# max14866.net
KiCad netlist of a schematic drawn in Altium Designer
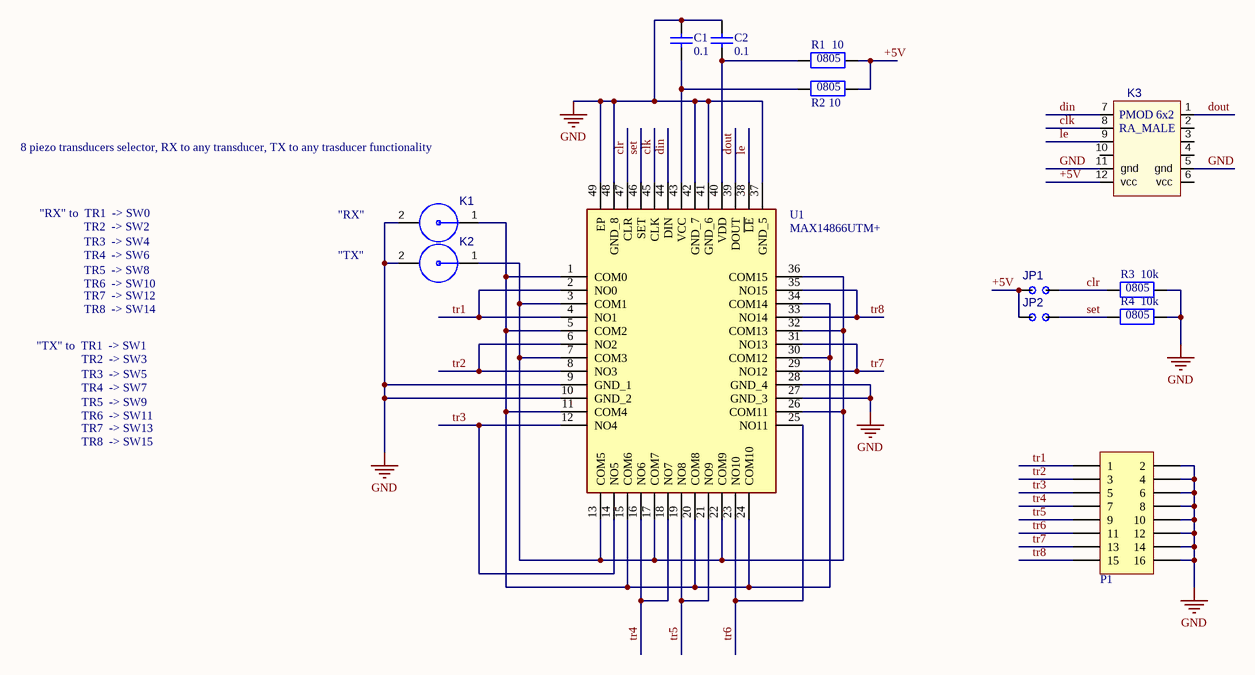
[diagram p0: max14866.SchDoc]

(export (version "E")
  (design (tool "Eeschema 10.0.6"))
  (components
    (comp (ref "C1")
      (value "0.1")
      (footprint "SM0805")
      (description "Capacitor")
      (fields (field (name "Comment") "cap0805") (field (name "PUBLISHER") "Altium Limited"))
      (libsource (lib "alt2017") (part "cap0805"))
    )
    (comp (ref "C2")
      (value "0.1")
      (footprint "SM0805")
      (description "Capacitor")
      (fields (field (name "Comment") "cap0805") (field (name "PUBLISHER") "Altium Limited"))
      (libsource (lib "alt2017") (part "cap0805"))
    )
    (comp (ref "JP1") (value "JUMPER2") (footprint "JUMPER2") (libsource (lib "alt2017") (part "JUMPER2")))
    (comp (ref "JP2") (value "JUMPER2") (footprint "JUMPER2") (libsource (lib "alt2017") (part "JUMPER2")))
    (comp (ref "K1")
      (value "SMA_MALE_with_NUT")
      (footprint "AMPHENOL_MALE")
      (libsource (lib "alt2017") (part "SMA_MALE_with_NUT"))
    )
    (comp (ref "K2")
      (value "SMA_MALE_with_NUT")
      (footprint "AMPHENOL_MALE")
      (libsource (lib "alt2017") (part "SMA_MALE_with_NUT"))
    )
    (comp (ref "K3")
      (value "PMOD_6x2_ra_male_mirrored")
      (footprint "PMOD_6x2_RA_MALE_MIRRORED")
      (description "PMOD_6x2_right_angle")
      (libsource (lib "alt2017") (part "PMOD_6x2_ra_male_mirrored"))
    )
    (comp (ref "P1")
      (value "2x8, 2.54mm vertical")
      (footprint "2x8 pin 2.54mm")
      (description "Header, 16-Pin")
      (fields (field (name "PUBLISHER") "Altium Limited"))
      (libsource (lib "alt2017") (part "2x8, 2.54mm, vertical"))
    )
    (comp (ref "R1")
      (value "10")
      (footprint "SM0805")
      (description "Resistor")
      (fields (field (name "Comment") "res0805_EU") (field (name "PUBLISHER") "Altium Limited"))
      (libsource (lib "alt2017") (part "res0805_EU"))
    )
    (comp (ref "R2")
      (value "10")
      (footprint "SM0805")
      (description "Resistor")
      (fields (field (name "Comment") "res0805_EU") (field (name "PUBLISHER") "Altium Limited"))
      (libsource (lib "alt2017") (part "res0805_EU"))
    )
    (comp (ref "R3")
      (value "10k")
      (footprint "SM0805")
      (description "Resistor")
      (fields (field (name "Comment") "res0805_EU") (field (name "PUBLISHER") "Altium Limited"))
      (libsource (lib "alt2017") (part "res0805_EU"))
    )
    (comp (ref "R4")
      (value "10k")
      (footprint "SM0805")
      (description "Resistor")
      (fields (field (name "Comment") "res0805_EU") (field (name "PUBLISHER") "Altium Limited"))
      (libsource (lib "alt2017") (part "res0805_EU"))
    )
    (comp (ref "U1")
      (value "MAX14866UTM+")
      (footprint "QFN50P700X700X80-49N")
      (description "Integrated Circuit")
      (fields (field (name "MOUSER PART NUMBER") "700-MAX14866UTM+"))
      (libsource (lib "alt2017") (part "MAX14866UTM+"))
    )
  )
  (nets
    (net (code "1") (name "/+5V") (class "Default")
      (node (ref "JP1") (pin "2") (pinfunction "2_2") (pintype "passive"))
      (node (ref "JP2") (pin "2") (pinfunction "2_2") (pintype "passive"))
      (node (ref "K3") (pin "12") (pinfunction "vcc_12") (pintype "passive"))
      (node (ref "R1") (pin "2") (pinfunction "2_2") (pintype "passive"))
      (node (ref "R2") (pin "2") (pinfunction "2_2") (pintype "passive"))
    )
    (net (code "2") (name "/clk") (class "Default")
      (node (ref "K3") (pin "8") (pinfunction "8_8") (pintype "passive"))
      (node (ref "U1") (pin "45") (pinfunction "CLK_45") (pintype "passive"))
    )
    (net (code "3") (name "/clr") (class "Default")
      (node (ref "JP1") (pin "1") (pinfunction "1_1") (pintype "passive"))
      (node (ref "R3") (pin "1") (pinfunction "1_1") (pintype "passive"))
      (node (ref "U1") (pin "47") (pinfunction "CLR_47") (pintype "passive"))
    )
    (net (code "4") (name "/din") (class "Default")
      (node (ref "K3") (pin "7") (pinfunction "7_7") (pintype "passive"))
      (node (ref "U1") (pin "44") (pinfunction "DIN_44") (pintype "passive"))
    )
    (net (code "5") (name "/dout") (class "Default")
      (node (ref "K3") (pin "1") (pinfunction "1_1") (pintype "passive"))
      (node (ref "U1") (pin "39") (pinfunction "DOUT_39") (pintype "passive"))
    )
    (net (code "6") (name "/le") (class "Default")
      (node (ref "K3") (pin "9") (pinfunction "9_9") (pintype "passive"))
      (node (ref "U1") (pin "38") (pinfunction "~{LE}_38") (pintype "passive"))
    )
    (net (code "7") (name "/set") (class "Default")
      (node (ref "JP2") (pin "1") (pinfunction "1_1") (pintype "passive"))
      (node (ref "R4") (pin "1") (pinfunction "1_1") (pintype "passive"))
      (node (ref "U1") (pin "46") (pinfunction "SET_46") (pintype "passive"))
    )
    (net (code "8") (name "/tr1") (class "Default")
      (node (ref "P1") (pin "1") (pinfunction "1_1") (pintype "passive"))
      (node (ref "U1") (pin "2") (pinfunction "NO0_2") (pintype "passive"))
      (node (ref "U1") (pin "4") (pinfunction "NO1_4") (pintype "passive"))
    )
    (net (code "9") (name "/tr2") (class "Default")
      (node (ref "P1") (pin "3") (pinfunction "3_3") (pintype "passive"))
      (node (ref "U1") (pin "6") (pinfunction "NO2_6") (pintype "passive"))
      (node (ref "U1") (pin "8") (pinfunction "NO3_8") (pintype "passive"))
    )
    (net (code "10") (name "/tr3") (class "Default")
      (node (ref "P1") (pin "5") (pinfunction "5_5") (pintype "passive"))
      (node (ref "U1") (pin "12") (pinfunction "NO4_12") (pintype "passive"))
      (node (ref "U1") (pin "14") (pinfunction "NO5_14") (pintype "passive"))
    )
    (net (code "11") (name "/tr4") (class "Default")
      (node (ref "P1") (pin "7") (pinfunction "7_7") (pintype "passive"))
      (node (ref "U1") (pin "16") (pinfunction "NO6_16") (pintype "passive"))
      (node (ref "U1") (pin "18") (pinfunction "NO7_18") (pintype "passive"))
    )
    (net (code "12") (name "/tr5") (class "Default")
      (node (ref "P1") (pin "9") (pinfunction "9_9") (pintype "passive"))
      (node (ref "U1") (pin "19") (pinfunction "NO8_19") (pintype "passive"))
      (node (ref "U1") (pin "21") (pinfunction "NO9_21") (pintype "passive"))
    )
    (net (code "13") (name "/tr6") (class "Default")
      (node (ref "P1") (pin "11") (pinfunction "11_11") (pintype "passive"))
      (node (ref "U1") (pin "23") (pinfunction "NO10_23") (pintype "passive"))
      (node (ref "U1") (pin "25") (pinfunction "NO11_25") (pintype "passive"))
    )
    (net (code "14") (name "/tr7") (class "Default")
      (node (ref "P1") (pin "13") (pinfunction "13_13") (pintype "passive"))
      (node (ref "U1") (pin "29") (pinfunction "NO12_29") (pintype "passive"))
      (node (ref "U1") (pin "31") (pinfunction "NO13_31") (pintype "passive"))
    )
    (net (code "15") (name "/tr8") (class "Default")
      (node (ref "P1") (pin "15") (pinfunction "15_15") (pintype "passive"))
      (node (ref "U1") (pin "33") (pinfunction "NO14_33") (pintype "passive"))
      (node (ref "U1") (pin "35") (pinfunction "NO15_35") (pintype "passive"))
    )
    (net (code "16") (name "GND") (class "Default")
      (node (ref "C1") (pin "2") (pinfunction "2_2") (pintype "passive"))
      (node (ref "C2") (pin "2") (pinfunction "2_2") (pintype "passive"))
      (node (ref "K1") (pin "2") (pinfunction "2_2") (pintype "passive"))
      (node (ref "K2") (pin "2") (pinfunction "2_2") (pintype "passive"))
      (node (ref "K3") (pin "11") (pinfunction "gnd_11") (pintype "passive"))
      (node (ref "K3") (pin "5") (pinfunction "gnd_5") (pintype "passive"))
      (node (ref "P1") (pin "10") (pinfunction "10_10") (pintype "passive"))
      (node (ref "P1") (pin "12") (pinfunction "12_12") (pintype "passive"))
      (node (ref "P1") (pin "14") (pinfunction "14_14") (pintype "passive"))
      (node (ref "P1") (pin "16") (pinfunction "16_16") (pintype "passive"))
      (node (ref "P1") (pin "2") (pinfunction "2_2") (pintype "passive"))
      (node (ref "P1") (pin "4") (pinfunction "4_4") (pintype "passive"))
      (node (ref "P1") (pin "6") (pinfunction "6_6") (pintype "passive"))
      (node (ref "P1") (pin "8") (pinfunction "8_8") (pintype "passive"))
      (node (ref "R3") (pin "2") (pinfunction "2_2") (pintype "passive"))
      (node (ref "R4") (pin "2") (pinfunction "2_2") (pintype "passive"))
      (node (ref "U1") (pin "10") (pinfunction "GND_2_10") (pintype "passive"))
      (node (ref "U1") (pin "27") (pinfunction "GND_3_27") (pintype "passive"))
      (node (ref "U1") (pin "28") (pinfunction "GND_4_28") (pintype "passive"))
      (node (ref "U1") (pin "37") (pinfunction "GND_5_37") (pintype "passive"))
      (node (ref "U1") (pin "41") (pinfunction "GND_6_41") (pintype "passive"))
      (node (ref "U1") (pin "42") (pinfunction "GND_7_42") (pintype "passive"))
      (node (ref "U1") (pin "48") (pinfunction "GND_8_48") (pintype "passive"))
      (node (ref "U1") (pin "49") (pinfunction "EP_49") (pintype "passive"))
      (node (ref "U1") (pin "9") (pinfunction "GND_1_9") (pintype "passive"))
    )
    (net (code "17") (name "Net-(U1-COM0)") (class "Default")
      (node (ref "K1") (pin "1") (pinfunction "1_1") (pintype "passive"))
      (node (ref "U1") (pin "1") (pinfunction "COM0_1") (pintype "passive"))
      (node (ref "U1") (pin "11") (pinfunction "COM4_11") (pintype "passive"))
      (node (ref "U1") (pin "15") (pinfunction "COM6_15") (pintype "passive"))
      (node (ref "U1") (pin "20") (pinfunction "COM8_20") (pintype "passive"))
      (node (ref "U1") (pin "24") (pinfunction "COM10_24") (pintype "passive"))
      (node (ref "U1") (pin "30") (pinfunction "COM12_30") (pintype "passive"))
      (node (ref "U1") (pin "34") (pinfunction "COM14_34") (pintype "passive"))
      (node (ref "U1") (pin "5") (pinfunction "COM2_5") (pintype "passive"))
    )
    (net (code "18") (name "Net-(U1-COM1)") (class "Default")
      (node (ref "K2") (pin "1") (pinfunction "1_1") (pintype "passive"))
      (node (ref "U1") (pin "13") (pinfunction "COM5_13") (pintype "passive"))
      (node (ref "U1") (pin "17") (pinfunction "COM7_17") (pintype "passive"))
      (node (ref "U1") (pin "22") (pinfunction "COM9_22") (pintype "passive"))
      (node (ref "U1") (pin "26") (pinfunction "COM11_26") (pintype "passive"))
      (node (ref "U1") (pin "3") (pinfunction "COM1_3") (pintype "passive"))
      (node (ref "U1") (pin "32") (pinfunction "COM13_32") (pintype "passive"))
      (node (ref "U1") (pin "36") (pinfunction "COM15_36") (pintype "passive"))
      (node (ref "U1") (pin "7") (pinfunction "COM3_7") (pintype "passive"))
    )
    (net (code "19") (name "Net-(U1-VCC)") (class "Default")
      (node (ref "C1") (pin "1") (pinfunction "1_1") (pintype "passive"))
      (node (ref "R2") (pin "1") (pinfunction "1_1") (pintype "passive"))
      (node (ref "U1") (pin "43") (pinfunction "VCC_43") (pintype "passive"))
    )
    (net (code "20") (name "Net-(U1-VDD)") (class "Default")
      (node (ref "C2") (pin "1") (pinfunction "1_1") (pintype "passive"))
      (node (ref "R1") (pin "1") (pinfunction "1_1") (pintype "passive"))
      (node (ref "U1") (pin "40") (pinfunction "VDD_40") (pintype "passive"))
    )
    (net (code "21") (name "unconnected-(K3-Pad2)") (class "Default")
      (node (ref "K3") (pin "2") (pinfunction "2_2") (pintype "passive"))
    )
    (net (code "22") (name "unconnected-(K3-Pad3)") (class "Default")
      (node (ref "K3") (pin "3") (pinfunction "3_3") (pintype "passive"))
    )
    (net (code "23") (name "unconnected-(K3-Pad4)") (class "Default")
      (node (ref "K3") (pin "4") (pinfunction "4_4") (pintype "passive"))
    )
    (net (code "24") (name "unconnected-(K3-Pad10)") (class "Default")
      (node (ref "K3") (pin "10") (pinfunction "10_10") (pintype "passive"))
    )
    (net (code "25") (name "unconnected-(K3-vcc-Pad6)") (class "Default")
      (node (ref "K3") (pin "6") (pinfunction "vcc_6") (pintype "passive"))
    )
  )
)
